# tinyProto_2026-02-20.net
KiCad netlist of a schematic drawn in EasyEDA Pro
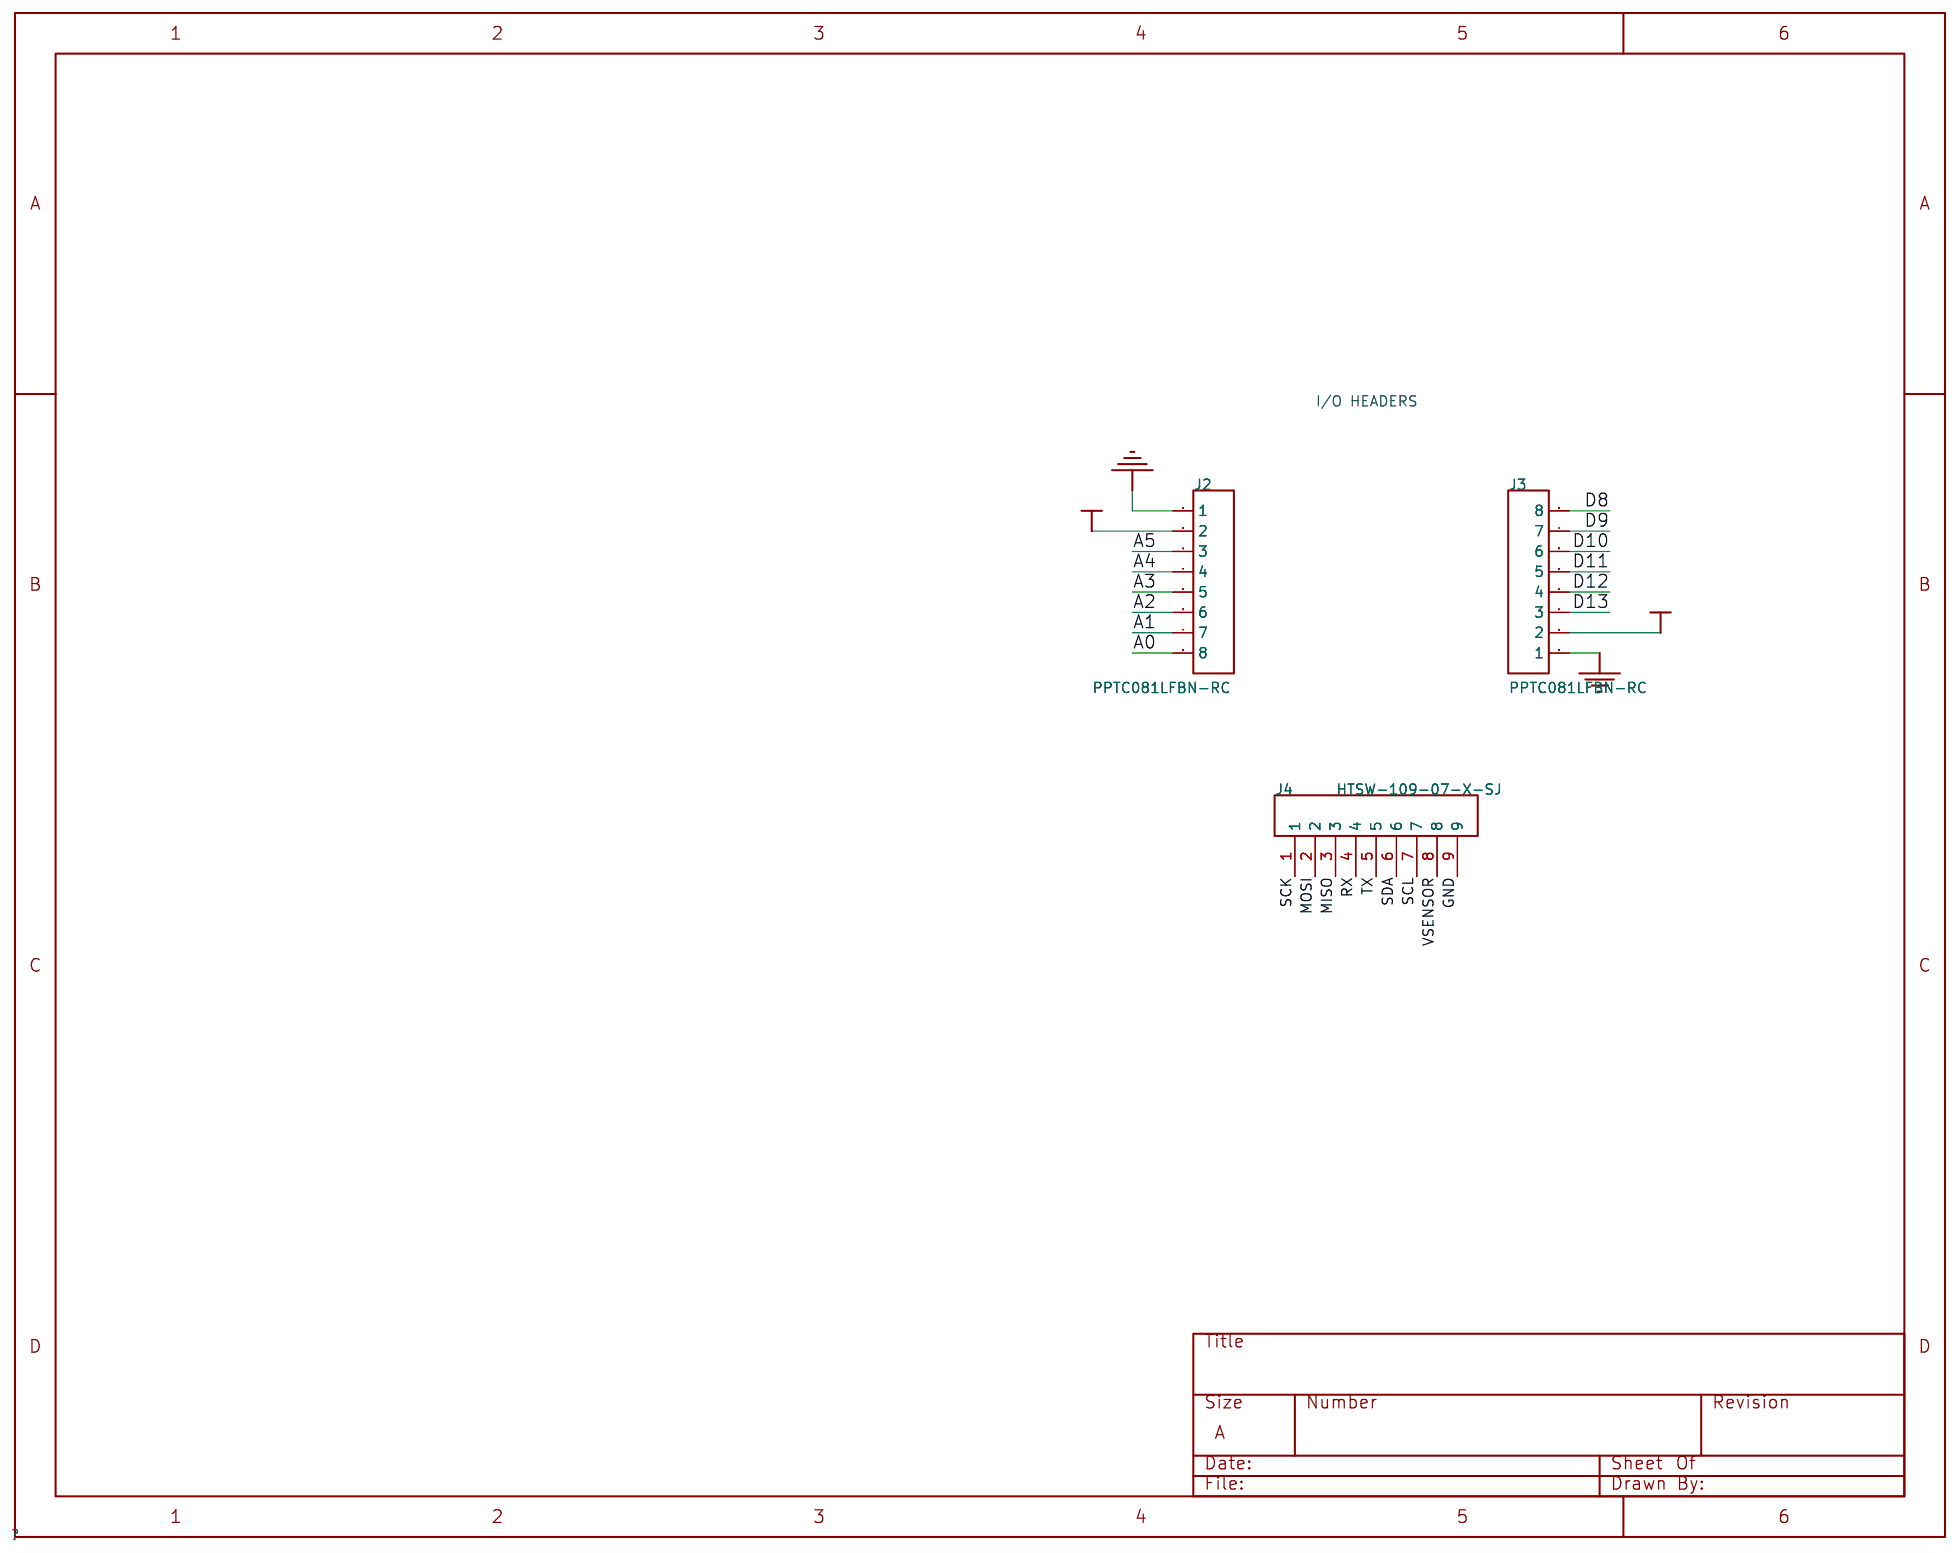
[diagram p0: schematic sheet]

(export (version "E")
  (design (tool "Eeschema 10.0.6"))
  (components
    (comp (ref "J2")
      (value "PPTC081LFBN-RC")
      (footprint "easyedapro:8_PIN_100MIL - Female")
      (description "8 Position Header Connector 0.100\" (2.54mm) Through Hole Tin")
      (fields (field (name "LCSC Part#") "C27438"))
      (libsource (lib "easyedapro") (part "JF_8_PIN_FEMALE"))
    )
    (comp (ref "J3")
      (value "PPTC081LFBN-RC")
      (footprint "easyedapro:8_PIN_100MIL - Female")
      (description "8 Position Header Connector 0.100\" (2.54mm) Through Hole Tin")
      (fields (field (name "LCSC Part#") "C27438"))
      (libsource (lib "easyedapro") (part "JF_8_PIN_FEMALE"))
    )
    (comp (ref "J4")
      (value "HTSW-109-07-X-SJ")
      (footprint "easyedapro:JM-9_HTSW-109-07-X-S")
      (description "2.54mm Black 1x9P Straight,P=2.54mm Pin Headers")
      (fields (field (name "LCSC PART#") "C2894932") (field (name "MFR PART #") "PZ254-1-09-Z-8.5"))
      (libsource (lib "easyedapro") (part "JM_9_PIN_MALE"))
    )
  )
  (nets
    (net (code "1") (name "/A0") (class "Default")
      (node (ref "J2") (pin "8") (pinfunction "8_8") (pintype "unspecified"))
    )
    (net (code "2") (name "/A1") (class "Default")
      (node (ref "J2") (pin "7") (pinfunction "7_7") (pintype "unspecified"))
    )
    (net (code "3") (name "/A2") (class "Default")
      (node (ref "J2") (pin "6") (pinfunction "6_6") (pintype "unspecified"))
    )
    (net (code "4") (name "/A3") (class "Default")
      (node (ref "J2") (pin "5") (pinfunction "5_5") (pintype "unspecified"))
    )
    (net (code "5") (name "/A4") (class "Default")
      (node (ref "J2") (pin "4") (pinfunction "4_4") (pintype "unspecified"))
    )
    (net (code "6") (name "/A5") (class "Default")
      (node (ref "J2") (pin "3") (pinfunction "3_3") (pintype "unspecified"))
    )
    (net (code "7") (name "/D8") (class "Default")
      (node (ref "J3") (pin "8") (pinfunction "8_8") (pintype "unspecified"))
    )
    (net (code "8") (name "/D9") (class "Default")
      (node (ref "J3") (pin "7") (pinfunction "7_7") (pintype "unspecified"))
    )
    (net (code "9") (name "/D10") (class "Default")
      (node (ref "J3") (pin "6") (pinfunction "6_6") (pintype "unspecified"))
    )
    (net (code "10") (name "/D11") (class "Default")
      (node (ref "J3") (pin "5") (pinfunction "5_5") (pintype "unspecified"))
    )
    (net (code "11") (name "/D12") (class "Default")
      (node (ref "J3") (pin "4") (pinfunction "4_4") (pintype "unspecified"))
    )
    (net (code "12") (name "/D13") (class "Default")
      (node (ref "J3") (pin "3") (pinfunction "3_3") (pintype "unspecified"))
    )
    (net (code "13") (name "/MISO") (class "Default")
      (node (ref "J4") (pin "3") (pinfunction "3_3") (pintype "unspecified"))
    )
    (net (code "14") (name "/MOSI") (class "Default")
      (node (ref "J4") (pin "2") (pinfunction "2_2") (pintype "unspecified"))
    )
    (net (code "15") (name "/RX") (class "Default")
      (node (ref "J4") (pin "4") (pinfunction "4_4") (pintype "unspecified"))
    )
    (net (code "16") (name "/SCK") (class "Default")
      (node (ref "J4") (pin "1") (pinfunction "1_1") (pintype "unspecified"))
    )
    (net (code "17") (name "/SCL") (class "Default")
      (node (ref "J4") (pin "7") (pinfunction "7_7") (pintype "unspecified"))
    )
    (net (code "18") (name "/SDA") (class "Default")
      (node (ref "J4") (pin "6") (pinfunction "6_6") (pintype "unspecified"))
    )
    (net (code "19") (name "/TX") (class "Default")
      (node (ref "J4") (pin "5") (pinfunction "5_5") (pintype "unspecified"))
    )
    (net (code "20") (name "/VSENSOR") (class "Default")
      (node (ref "J4") (pin "8") (pinfunction "8_8") (pintype "unspecified"))
    )
    (net (code "21") (name "3V3") (class "Default")
      (node (ref "J2") (pin "2") (pinfunction "2_2") (pintype "unspecified"))
      (node (ref "J3") (pin "2") (pinfunction "2_2") (pintype "unspecified"))
    )
    (net (code "22") (name "GND") (class "Default")
      (node (ref "J2") (pin "1") (pinfunction "1_1") (pintype "unspecified"))
      (node (ref "J3") (pin "1") (pinfunction "1_1") (pintype "unspecified"))
      (node (ref "J4") (pin "9") (pinfunction "9_9") (pintype "unspecified"))
    )
  )
)
